# So1urce.net
KiCad netlist of a schematic drawn in EasyEDA Pro
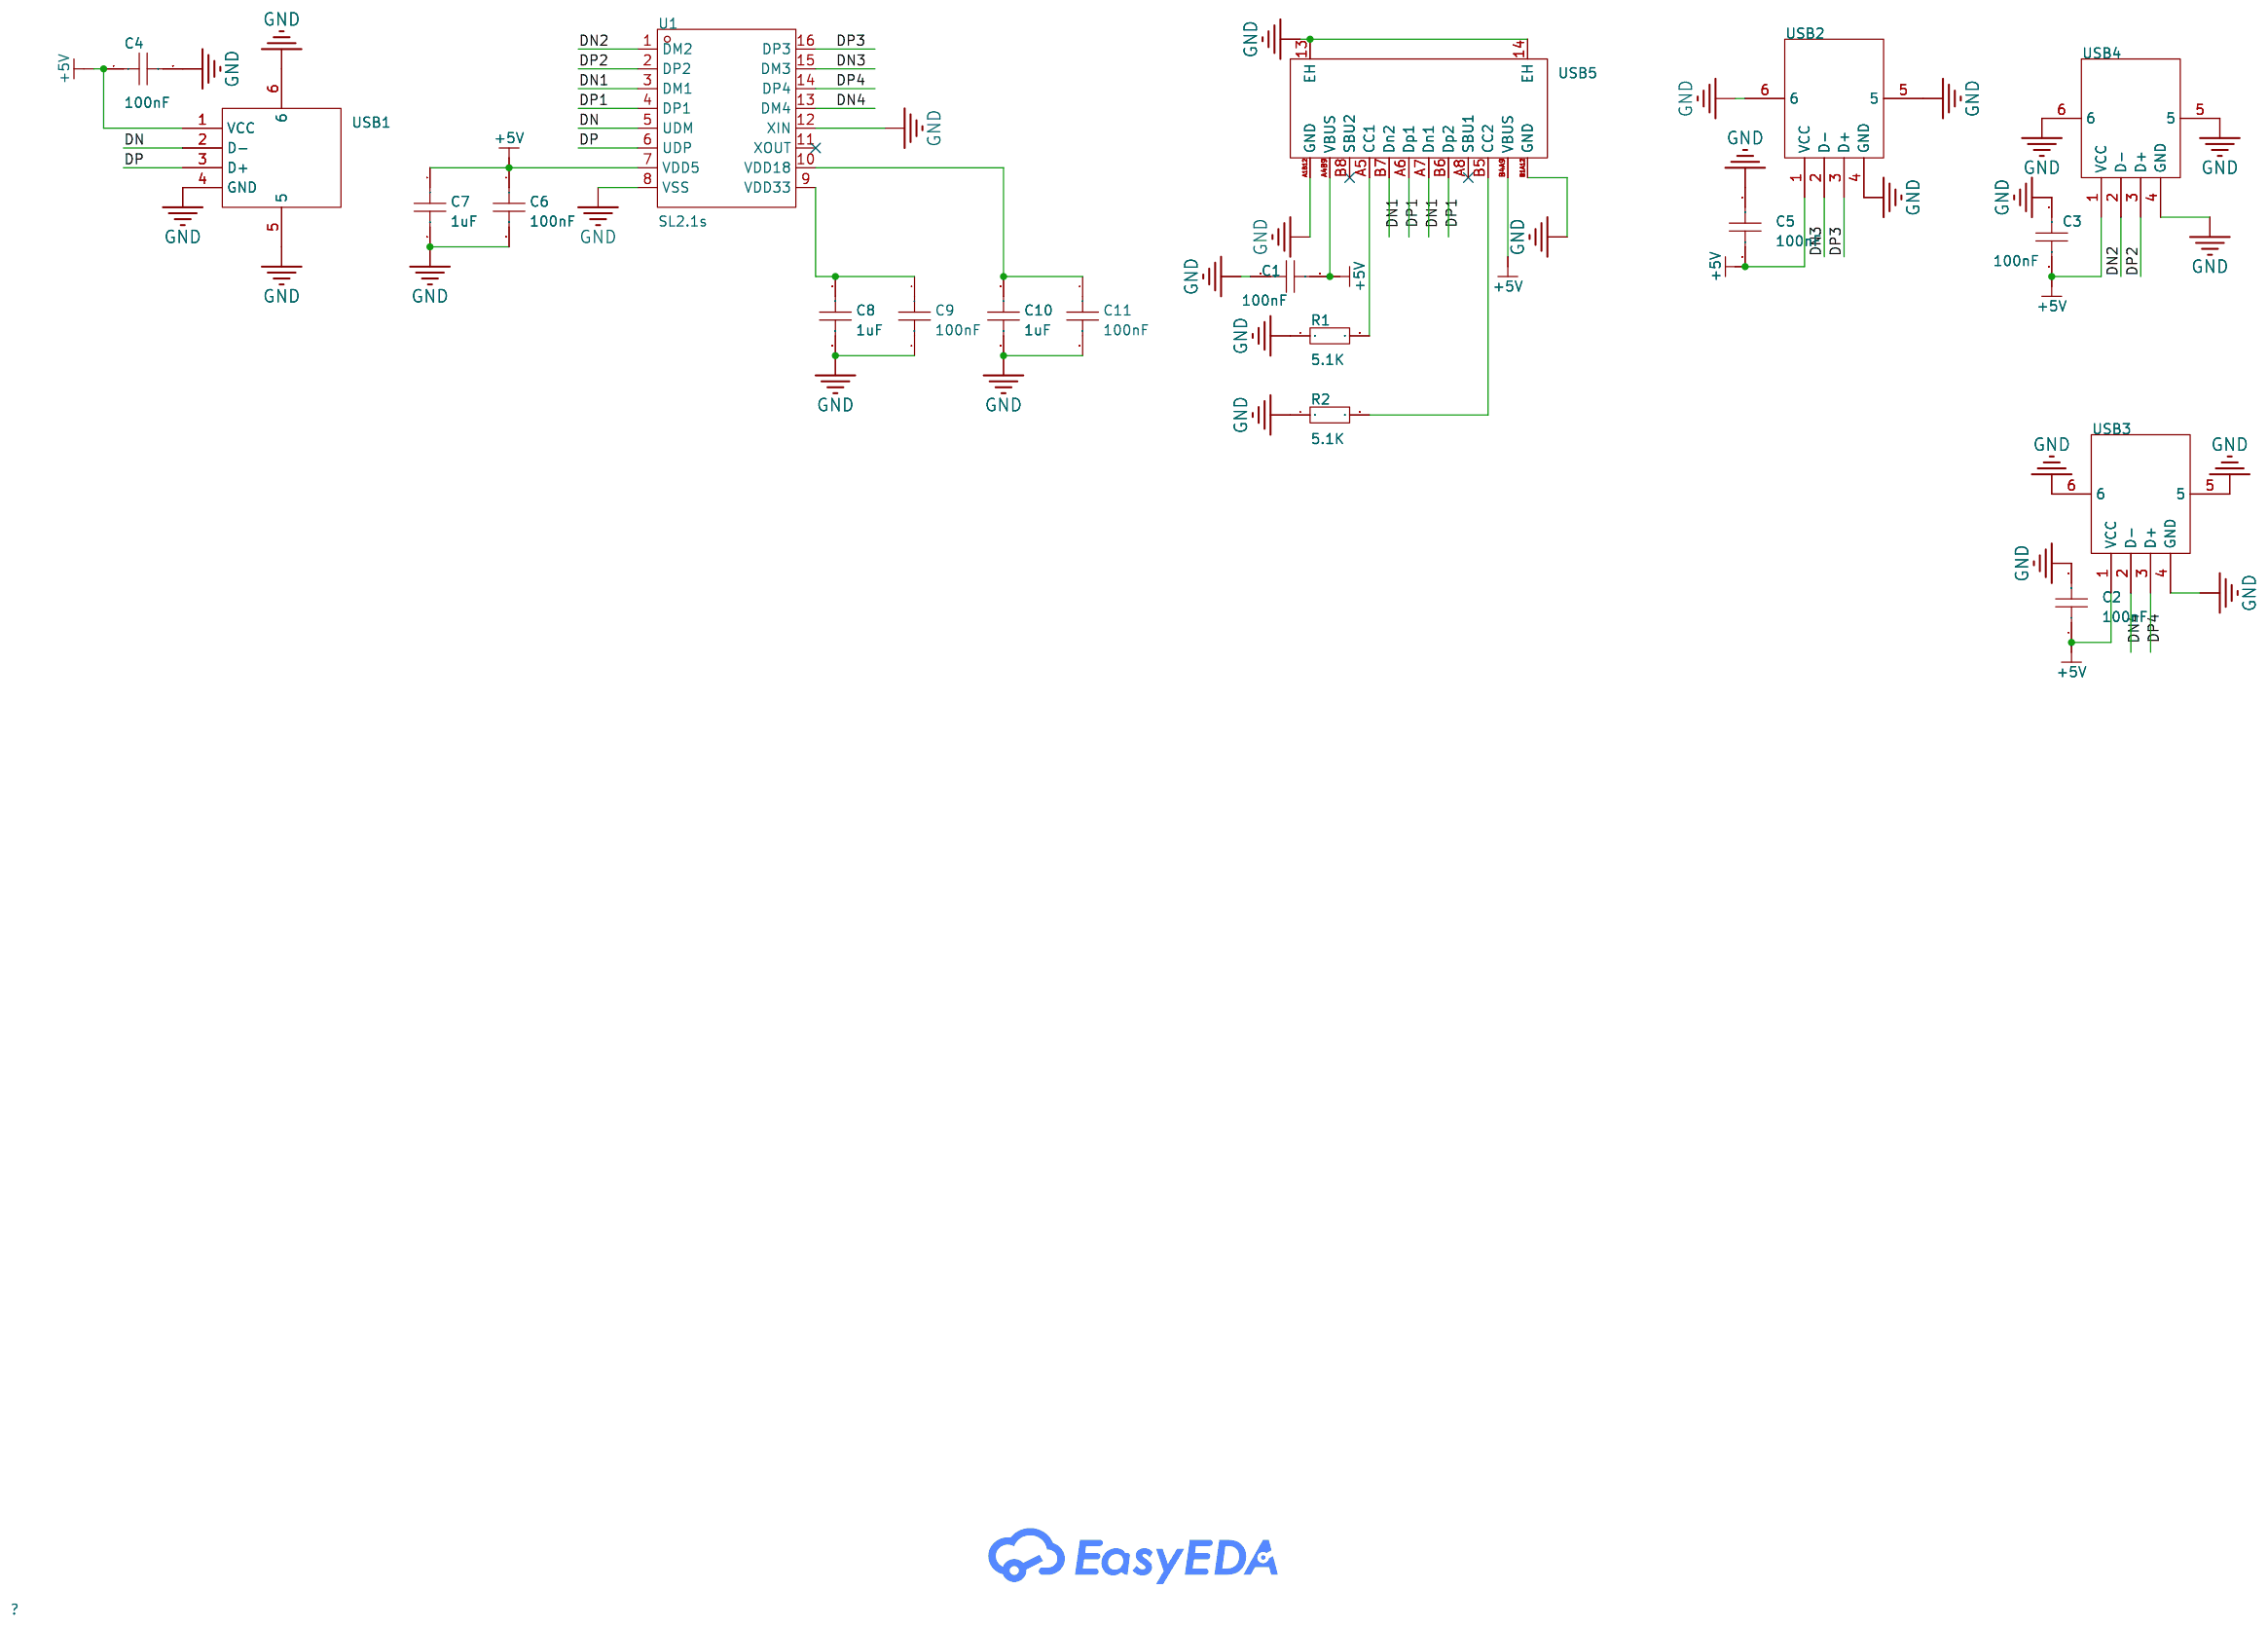
[diagram p0: schematic sheet]

(export (version "E")
  (design (tool "Eeschema 10.0.6"))
  (components
    (comp (ref "C1")
      (value "100nF")
      (footprint "easyedapro:C0603")
      (libsource (lib "easyedapro") (part "CAP"))
    )
    (comp (ref "C2")
      (value "100nF")
      (footprint "easyedapro:C0603")
      (libsource (lib "easyedapro") (part "CAP"))
    )
    (comp (ref "C3")
      (value "100nF")
      (footprint "easyedapro:C0603")
      (libsource (lib "easyedapro") (part "CAP"))
    )
    (comp (ref "C4")
      (value "100nF")
      (footprint "easyedapro:C0603")
      (libsource (lib "easyedapro") (part "CAP"))
    )
    (comp (ref "C5")
      (value "100nF")
      (footprint "easyedapro:C0603")
      (libsource (lib "easyedapro") (part "CAP"))
    )
    (comp (ref "C6")
      (value "100nF")
      (footprint "easyedapro:C0603")
      (libsource (lib "easyedapro") (part "CAP"))
    )
    (comp (ref "C7") (value "1uF") (footprint "easyedapro:C0603") (libsource (lib "easyedapro") (part "CAP")))
    (comp (ref "C8") (value "1uF") (footprint "easyedapro:C0603") (libsource (lib "easyedapro") (part "CAP")))
    (comp (ref "C9")
      (value "100nF")
      (footprint "easyedapro:C0603")
      (libsource (lib "easyedapro") (part "CAP"))
    )
    (comp (ref "C10")
      (value "1uF")
      (footprint "easyedapro:C0603")
      (libsource (lib "easyedapro") (part "CAP"))
    )
    (comp (ref "C11")
      (value "100nF")
      (footprint "easyedapro:C0603")
      (libsource (lib "easyedapro") (part "CAP"))
    )
    (comp (ref "R1")
      (value "5.1K")
      (footprint "easyedapro:R0603")
      (libsource (lib "easyedapro") (part "Res"))
    )
    (comp (ref "R2")
      (value "5.1K")
      (footprint "easyedapro:R0603")
      (libsource (lib "easyedapro") (part "Res"))
    )
    (comp (ref "U1")
      (value "SL2.1s")
      (footprint "easyedapro:SSOP-16_L4.6-W2.6-P0.53-LS4.0-BL")
      (fields (field (name "Manufacturer") "CoreChips(和芯润德)"))
      (libsource (lib "easyedapro") (part "SL2.1S"))
    )
    (comp (ref "USB1")
      (value "10.0 QHHTZB6.3")
      (footprint "easyedapro:USB-A-TH_10.0QHHTZB6.3")
      (fields (field (name "Manufacturer") "SHOU HAN(首韩)"))
      (libsource (lib "easyedapro") (part "10.0 QHHTZB6.3"))
    )
    (comp (ref "USB2")
      (value "10.0 QHHTZB6.3")
      (footprint "easyedapro:USB-A-TH_10.0QHHTZB6.3")
      (fields (field (name "Manufacturer") "SHOU HAN(首韩)"))
      (libsource (lib "easyedapro") (part "10.0 QHHTZB6.3"))
    )
    (comp (ref "USB3")
      (value "10.0 QHHTZB6.3")
      (footprint "easyedapro:USB-A-TH_10.0QHHTZB6.3")
      (fields (field (name "Manufacturer") "SHOU HAN(首韩)"))
      (libsource (lib "easyedapro") (part "10.0 QHHTZB6.3"))
    )
    (comp (ref "USB4")
      (value "10.0 QHHTZB6.3")
      (footprint "easyedapro:USB-A-TH_10.0QHHTZB6.3")
      (fields (field (name "Manufacturer") "SHOU HAN(首韩)"))
      (libsource (lib "easyedapro") (part "10.0 QHHTZB6.3"))
    )
    (comp (ref "USB5")
      (value "TYPE-C 16PIN 2MD(073)")
      (footprint "easyedapro:USB-C-SMD_TYPE-C-16PIN-2MD-073")
      (fields (field (name "Manufacturer") "SHOU HAN(首韩)"))
      (libsource (lib "easyedapro") (part "TYPE-C 16PIN 2MD(073)"))
    )
  )
  (nets
    (net (code "1") (name "+5V") (class "Default")
      (node (ref "C1") (pin "1") (pinfunction "1_1") (pintype "input"))
      (node (ref "C2") (pin "1") (pinfunction "1_1") (pintype "input"))
      (node (ref "C3") (pin "2") (pinfunction "2_2") (pintype "input"))
      (node (ref "C4") (pin "1") (pinfunction "1_1") (pintype "input"))
      (node (ref "C5") (pin "2") (pinfunction "2_2") (pintype "input"))
      (node (ref "C6") (pin "1") (pinfunction "1_1") (pintype "input"))
      (node (ref "C7") (pin "1") (pinfunction "1_1") (pintype "input"))
      (node (ref "U1") (pin "7") (pinfunction "VDD5_7") (pintype "unspecified"))
      (node (ref "USB1") (pin "1") (pinfunction "VCC_1") (pintype "unspecified"))
      (node (ref "USB2") (pin "1") (pinfunction "VCC_1") (pintype "unspecified"))
      (node (ref "USB3") (pin "1") (pinfunction "VCC_1") (pintype "unspecified"))
      (node (ref "USB4") (pin "1") (pinfunction "VCC_1") (pintype "unspecified"))
      (node (ref "USB5") (pin "A4B9") (pinfunction "VBUS_A4B9") (pintype "unspecified"))
      (node (ref "USB5") (pin "B4A9") (pinfunction "VBUS_B4A9") (pintype "unspecified"))
    )
    (net (code "2") (name "/DN") (class "Default")
      (node (ref "U1") (pin "5") (pinfunction "UDM_5") (pintype "unspecified"))
      (node (ref "USB1") (pin "2") (pinfunction "D-_2") (pintype "unspecified"))
    )
    (net (code "3") (name "/DN1") (class "Default")
      (node (ref "U1") (pin "3") (pinfunction "DM1_3") (pintype "unspecified"))
      (node (ref "USB5") (pin "A7") (pinfunction "Dn1_A7") (pintype "unspecified"))
      (node (ref "USB5") (pin "B7") (pinfunction "Dn2_B7") (pintype "unspecified"))
    )
    (net (code "4") (name "/DN2") (class "Default")
      (node (ref "U1") (pin "1") (pinfunction "DM2_1") (pintype "unspecified"))
      (node (ref "USB4") (pin "2") (pinfunction "D-_2") (pintype "unspecified"))
    )
    (net (code "5") (name "/DN3") (class "Default")
      (node (ref "U1") (pin "15") (pinfunction "DM3_15") (pintype "unspecified"))
      (node (ref "USB2") (pin "2") (pinfunction "D-_2") (pintype "unspecified"))
    )
    (net (code "6") (name "/DN4") (class "Default")
      (node (ref "U1") (pin "13") (pinfunction "DM4_13") (pintype "unspecified"))
      (node (ref "USB3") (pin "2") (pinfunction "D-_2") (pintype "unspecified"))
    )
    (net (code "7") (name "/DP") (class "Default")
      (node (ref "U1") (pin "6") (pinfunction "UDP_6") (pintype "unspecified"))
      (node (ref "USB1") (pin "3") (pinfunction "D+_3") (pintype "unspecified"))
    )
    (net (code "8") (name "/DP1") (class "Default")
      (node (ref "U1") (pin "4") (pinfunction "DP1_4") (pintype "unspecified"))
      (node (ref "USB5") (pin "A6") (pinfunction "Dp1_A6") (pintype "unspecified"))
      (node (ref "USB5") (pin "B6") (pinfunction "Dp2_B6") (pintype "unspecified"))
    )
    (net (code "9") (name "/DP2") (class "Default")
      (node (ref "U1") (pin "2") (pinfunction "DP2_2") (pintype "unspecified"))
      (node (ref "USB4") (pin "3") (pinfunction "D+_3") (pintype "unspecified"))
    )
    (net (code "10") (name "/DP3") (class "Default")
      (node (ref "U1") (pin "16") (pinfunction "DP3_16") (pintype "unspecified"))
      (node (ref "USB2") (pin "3") (pinfunction "D+_3") (pintype "unspecified"))
    )
    (net (code "11") (name "/DP4") (class "Default")
      (node (ref "U1") (pin "14") (pinfunction "DP4_14") (pintype "unspecified"))
      (node (ref "USB3") (pin "3") (pinfunction "D+_3") (pintype "unspecified"))
    )
    (net (code "12") (name "GND") (class "Default")
      (node (ref "C1") (pin "2") (pinfunction "2_2") (pintype "input"))
      (node (ref "C10") (pin "2") (pinfunction "2_2") (pintype "input"))
      (node (ref "C11") (pin "2") (pinfunction "2_2") (pintype "input"))
      (node (ref "C2") (pin "2") (pinfunction "2_2") (pintype "input"))
      (node (ref "C3") (pin "1") (pinfunction "1_1") (pintype "input"))
      (node (ref "C4") (pin "2") (pinfunction "2_2") (pintype "input"))
      (node (ref "C5") (pin "1") (pinfunction "1_1") (pintype "input"))
      (node (ref "C6") (pin "2") (pinfunction "2_2") (pintype "input"))
      (node (ref "C7") (pin "2") (pinfunction "2_2") (pintype "input"))
      (node (ref "C8") (pin "2") (pinfunction "2_2") (pintype "input"))
      (node (ref "C9") (pin "2") (pinfunction "2_2") (pintype "input"))
      (node (ref "R1") (pin "1") (pinfunction "1_1") (pintype "input"))
      (node (ref "R2") (pin "1") (pinfunction "1_1") (pintype "input"))
      (node (ref "U1") (pin "12") (pinfunction "XIN_12") (pintype "unspecified"))
      (node (ref "U1") (pin "8") (pinfunction "VSS_8") (pintype "unspecified"))
      (node (ref "USB1") (pin "4") (pinfunction "GND_4") (pintype "unspecified"))
      (node (ref "USB1") (pin "5") (pinfunction "5_5") (pintype "unspecified"))
      (node (ref "USB1") (pin "6") (pinfunction "6_6") (pintype "unspecified"))
      (node (ref "USB2") (pin "4") (pinfunction "GND_4") (pintype "unspecified"))
      (node (ref "USB2") (pin "5") (pinfunction "5_5") (pintype "unspecified"))
      (node (ref "USB2") (pin "6") (pinfunction "6_6") (pintype "unspecified"))
      (node (ref "USB3") (pin "4") (pinfunction "GND_4") (pintype "unspecified"))
      (node (ref "USB3") (pin "5") (pinfunction "5_5") (pintype "unspecified"))
      (node (ref "USB3") (pin "6") (pinfunction "6_6") (pintype "unspecified"))
      (node (ref "USB4") (pin "4") (pinfunction "GND_4") (pintype "unspecified"))
      (node (ref "USB4") (pin "5") (pinfunction "5_5") (pintype "unspecified"))
      (node (ref "USB4") (pin "6") (pinfunction "6_6") (pintype "unspecified"))
      (node (ref "USB5") (pin "13") (pinfunction "EH_13") (pintype "unspecified"))
      (node (ref "USB5") (pin "14") (pinfunction "EH_14") (pintype "unspecified"))
      (node (ref "USB5") (pin "A1B12") (pinfunction "GND_A1B12") (pintype "unspecified"))
      (node (ref "USB5") (pin "B1A12") (pinfunction "GND_B1A12") (pintype "unspecified"))
    )
    (net (code "13") (name "Net-(U1-VDD18)") (class "Default")
      (node (ref "C10") (pin "1") (pinfunction "1_1") (pintype "input"))
      (node (ref "C11") (pin "1") (pinfunction "1_1") (pintype "input"))
      (node (ref "U1") (pin "10") (pinfunction "VDD18_10") (pintype "unspecified"))
    )
    (net (code "14") (name "Net-(U1-VDD33)") (class "Default")
      (node (ref "C8") (pin "1") (pinfunction "1_1") (pintype "input"))
      (node (ref "C9") (pin "1") (pinfunction "1_1") (pintype "input"))
      (node (ref "U1") (pin "9") (pinfunction "VDD33_9") (pintype "unspecified"))
    )
    (net (code "15") (name "Net-(USB5-CC1)") (class "Default")
      (node (ref "R1") (pin "2") (pinfunction "2_2") (pintype "input"))
      (node (ref "USB5") (pin "A5") (pinfunction "CC1_A5") (pintype "unspecified"))
    )
    (net (code "16") (name "Net-(USB5-CC2)") (class "Default")
      (node (ref "R2") (pin "2") (pinfunction "2_2") (pintype "input"))
      (node (ref "USB5") (pin "B5") (pinfunction "CC2_B5") (pintype "unspecified"))
    )
    (net (code "17") (name "unconnected-(U1-XOUT-Pad11)") (class "Default")
      (node (ref "U1") (pin "11") (pinfunction "XOUT_11") (pintype "unspecified+no_connect"))
    )
    (net (code "18") (name "unconnected-(USB5-SBU1-PadA8)") (class "Default")
      (node (ref "USB5") (pin "A8") (pinfunction "SBU1_A8") (pintype "unspecified+no_connect"))
    )
    (net (code "19") (name "unconnected-(USB5-SBU2-PadB8)") (class "Default")
      (node (ref "USB5") (pin "B8") (pinfunction "SBU2_B8") (pintype "unspecified+no_connect"))
    )
  )
)
